# v1.net
KiCad netlist of a schematic drawn in EAGLE
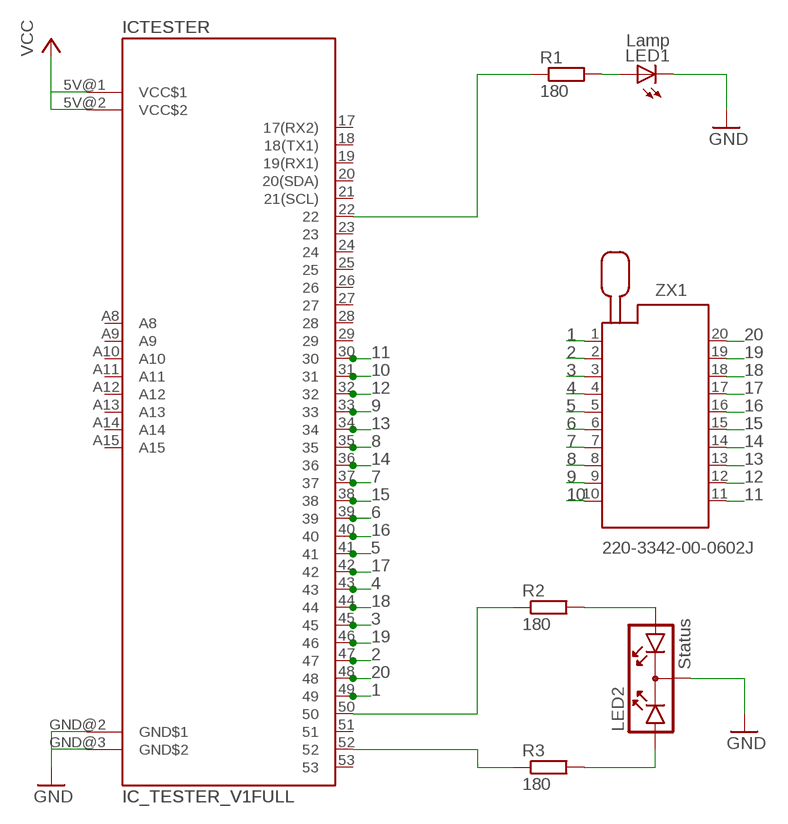
[diagram p0: schematic, sheet 1]

(export (version "E")
  (design (tool "Eeschema 10.0.6"))
  (components
    (comp (ref "ICTESTER")
      (value "IC_TESTER_V1FULL")
      (footprint "eagle-import:SPARKFUN-BOARDS_ARDUINO_MEGA")
      (libsource (lib "eagle-import") (part "IC_TESTER_V1FULL"))
    )
    (comp (ref "LED1")
      (value "Lamp")
      (footprint "eagle-import:LED3MM")
      (libsource (lib "eagle-import") (part "LED3MM"))
    )
    (comp (ref "LED2")
      (value "Status")
      (footprint "eagle-import:DUOLED")
      (libsource (lib "eagle-import") (part "DUOLED"))
    )
    (comp (ref "R1")
      (value "180")
      (footprint "eagle-import:0204V")
      (libsource (lib "eagle-import") (part "R-EU_0204/2V"))
    )
    (comp (ref "R2")
      (value "180")
      (footprint "eagle-import:0204V")
      (libsource (lib "eagle-import") (part "R-EU_0204/2V"))
    )
    (comp (ref "R3")
      (value "180")
      (footprint "eagle-import:0204V")
      (libsource (lib "eagle-import") (part "R-EU_0204/2V"))
    )
    (comp (ref "ZX1")
      (value "220-3342-00-0602J")
      (footprint "eagle-import:220-3342-00-0602J")
      (fields (field (name "MF") "3M"))
      (libsource (lib "eagle-import") (part "220-3342-00-0602J"))
    )
  )
  (nets
    (net (code "1") (name "/1") (class "Default")
      (node (ref "ICTESTER") (pin "49") (pinfunction "49_49") (pintype "bidirectional"))
      (node (ref "ZX1") (pin "1") (pinfunction "1_1") (pintype "passive"))
    )
    (net (code "2") (name "/2") (class "Default")
      (node (ref "ICTESTER") (pin "47") (pinfunction "47_47") (pintype "bidirectional"))
      (node (ref "ZX1") (pin "2") (pinfunction "2_2") (pintype "passive"))
    )
    (net (code "3") (name "/3") (class "Default")
      (node (ref "ICTESTER") (pin "45") (pinfunction "45_45") (pintype "bidirectional"))
      (node (ref "ZX1") (pin "3") (pinfunction "3_3") (pintype "passive"))
    )
    (net (code "4") (name "/4") (class "Default")
      (node (ref "ICTESTER") (pin "43") (pinfunction "43_43") (pintype "bidirectional"))
      (node (ref "ZX1") (pin "4") (pinfunction "4_4") (pintype "passive"))
    )
    (net (code "5") (name "/5") (class "Default")
      (node (ref "ICTESTER") (pin "41") (pinfunction "41_41") (pintype "bidirectional"))
      (node (ref "ZX1") (pin "5") (pinfunction "5_5") (pintype "passive"))
    )
    (net (code "6") (name "/6") (class "Default")
      (node (ref "ICTESTER") (pin "39") (pinfunction "39_39") (pintype "bidirectional"))
      (node (ref "ZX1") (pin "6") (pinfunction "6_6") (pintype "passive"))
    )
    (net (code "7") (name "/7") (class "Default")
      (node (ref "ICTESTER") (pin "37") (pinfunction "37_37") (pintype "bidirectional"))
      (node (ref "ZX1") (pin "7") (pinfunction "7_7") (pintype "passive"))
    )
    (net (code "8") (name "/8") (class "Default")
      (node (ref "ICTESTER") (pin "35") (pinfunction "35_35") (pintype "bidirectional"))
      (node (ref "ZX1") (pin "8") (pinfunction "8_8") (pintype "passive"))
    )
    (net (code "9") (name "/9") (class "Default")
      (node (ref "ICTESTER") (pin "33") (pinfunction "33_33") (pintype "bidirectional"))
      (node (ref "ZX1") (pin "9") (pinfunction "9_9") (pintype "passive"))
    )
    (net (code "10") (name "/10") (class "Default")
      (node (ref "ICTESTER") (pin "31") (pinfunction "31_31") (pintype "bidirectional"))
      (node (ref "ZX1") (pin "10") (pinfunction "10_10") (pintype "passive"))
    )
    (net (code "11") (name "/11") (class "Default")
      (node (ref "ICTESTER") (pin "30") (pinfunction "30_30") (pintype "bidirectional"))
      (node (ref "ZX1") (pin "11") (pinfunction "11_11") (pintype "passive"))
    )
    (net (code "12") (name "/12") (class "Default")
      (node (ref "ICTESTER") (pin "32") (pinfunction "32_32") (pintype "bidirectional"))
      (node (ref "ZX1") (pin "12") (pinfunction "12_12") (pintype "passive"))
    )
    (net (code "13") (name "/13") (class "Default")
      (node (ref "ICTESTER") (pin "34") (pinfunction "34_34") (pintype "bidirectional"))
      (node (ref "ZX1") (pin "13") (pinfunction "13_13") (pintype "passive"))
    )
    (net (code "14") (name "/14") (class "Default")
      (node (ref "ICTESTER") (pin "36") (pinfunction "36_36") (pintype "bidirectional"))
      (node (ref "ZX1") (pin "14") (pinfunction "14_14") (pintype "passive"))
    )
    (net (code "15") (name "/15") (class "Default")
      (node (ref "ICTESTER") (pin "38") (pinfunction "38_38") (pintype "bidirectional"))
      (node (ref "ZX1") (pin "15") (pinfunction "15_15") (pintype "passive"))
    )
    (net (code "16") (name "/16") (class "Default")
      (node (ref "ICTESTER") (pin "40") (pinfunction "40_40") (pintype "bidirectional"))
      (node (ref "ZX1") (pin "16") (pinfunction "16_16") (pintype "passive"))
    )
    (net (code "17") (name "/17") (class "Default")
      (node (ref "ICTESTER") (pin "42") (pinfunction "42_42") (pintype "bidirectional"))
      (node (ref "ZX1") (pin "17") (pinfunction "17_17") (pintype "passive"))
    )
    (net (code "18") (name "/18") (class "Default")
      (node (ref "ICTESTER") (pin "44") (pinfunction "44_44") (pintype "bidirectional"))
      (node (ref "ZX1") (pin "18") (pinfunction "18_18") (pintype "passive"))
    )
    (net (code "19") (name "/19") (class "Default")
      (node (ref "ICTESTER") (pin "46") (pinfunction "46_46") (pintype "bidirectional"))
      (node (ref "ZX1") (pin "19") (pinfunction "19_19") (pintype "passive"))
    )
    (net (code "20") (name "/20") (class "Default")
      (node (ref "ICTESTER") (pin "48") (pinfunction "48_48") (pintype "bidirectional"))
      (node (ref "ZX1") (pin "20") (pinfunction "20_20") (pintype "passive"))
    )
    (net (code "21") (name "GND") (class "Default")
      (node (ref "ICTESTER") (pin "GND@2") (pinfunction "GND$1_GND@2") (pintype "power_in"))
      (node (ref "ICTESTER") (pin "GND@3") (pinfunction "GND$2_GND@3") (pintype "power_in"))
      (node (ref "LED1") (pin "K") (pinfunction "C_K") (pintype "passive"))
      (node (ref "LED2") (pin "K") (pinfunction "K_K") (pintype "passive"))
    )
    (net (code "22") (name "Net-(ICTESTER-Pad22)") (class "Default")
      (node (ref "ICTESTER") (pin "22") (pinfunction "22_22") (pintype "bidirectional"))
      (node (ref "R1") (pin "1") (pinfunction "1_1") (pintype "passive"))
    )
    (net (code "23") (name "Net-(ICTESTER-Pad50)") (class "Default")
      (node (ref "ICTESTER") (pin "50") (pinfunction "50_50") (pintype "bidirectional"))
      (node (ref "R2") (pin "1") (pinfunction "1_1") (pintype "passive"))
    )
    (net (code "24") (name "Net-(ICTESTER-Pad52)") (class "Default")
      (node (ref "ICTESTER") (pin "52") (pinfunction "52_52") (pintype "bidirectional"))
      (node (ref "R3") (pin "1") (pinfunction "1_1") (pintype "passive"))
    )
    (net (code "25") (name "Net-(LED1-PadA)") (class "Default")
      (node (ref "LED1") (pin "A") (pinfunction "A_A") (pintype "passive"))
      (node (ref "R1") (pin "2") (pinfunction "2_2") (pintype "passive"))
    )
    (net (code "26") (name "Net-(LED2-PadA1)") (class "Default")
      (node (ref "LED2") (pin "A1") (pinfunction "A1_A1") (pintype "passive"))
      (node (ref "R3") (pin "2") (pinfunction "2_2") (pintype "passive"))
    )
    (net (code "27") (name "Net-(LED2-PadA2)") (class "Default")
      (node (ref "LED2") (pin "A2") (pinfunction "A2_A2") (pintype "passive"))
      (node (ref "R2") (pin "2") (pinfunction "2_2") (pintype "passive"))
    )
    (net (code "28") (name "VCC") (class "Default")
      (node (ref "ICTESTER") (pin "5V@1") (pinfunction "VCC$1_5V@1") (pintype "power_in"))
      (node (ref "ICTESTER") (pin "5V@2") (pinfunction "VCC$2_5V@2") (pintype "power_in"))
    )
    (net (code "29") (name "unconnected-(ICTESTER-17(RX2)-Pad17)") (class "Default")
      (node (ref "ICTESTER") (pin "17") (pinfunction "17(RX2)_17") (pintype "bidirectional"))
    )
    (net (code "30") (name "unconnected-(ICTESTER-18(TX1)-Pad18)") (class "Default")
      (node (ref "ICTESTER") (pin "18") (pinfunction "18(TX1)_18") (pintype "bidirectional"))
    )
    (net (code "31") (name "unconnected-(ICTESTER-19(RX1)-Pad19)") (class "Default")
      (node (ref "ICTESTER") (pin "19") (pinfunction "19(RX1)_19") (pintype "bidirectional"))
    )
    (net (code "32") (name "unconnected-(ICTESTER-20(SDA)-Pad20)") (class "Default")
      (node (ref "ICTESTER") (pin "20") (pinfunction "20(SDA)_20") (pintype "bidirectional"))
    )
    (net (code "33") (name "unconnected-(ICTESTER-21(SCL)-Pad21)") (class "Default")
      (node (ref "ICTESTER") (pin "21") (pinfunction "21(SCL)_21") (pintype "bidirectional"))
    )
    (net (code "34") (name "unconnected-(ICTESTER-Pad23)") (class "Default")
      (node (ref "ICTESTER") (pin "23") (pinfunction "23_23") (pintype "bidirectional"))
    )
    (net (code "35") (name "unconnected-(ICTESTER-Pad24)") (class "Default")
      (node (ref "ICTESTER") (pin "24") (pinfunction "24_24") (pintype "bidirectional"))
    )
    (net (code "36") (name "unconnected-(ICTESTER-Pad25)") (class "Default")
      (node (ref "ICTESTER") (pin "25") (pinfunction "25_25") (pintype "bidirectional"))
    )
    (net (code "37") (name "unconnected-(ICTESTER-Pad26)") (class "Default")
      (node (ref "ICTESTER") (pin "26") (pinfunction "26_26") (pintype "bidirectional"))
    )
    (net (code "38") (name "unconnected-(ICTESTER-Pad27)") (class "Default")
      (node (ref "ICTESTER") (pin "27") (pinfunction "27_27") (pintype "bidirectional"))
    )
    (net (code "39") (name "unconnected-(ICTESTER-Pad28)") (class "Default")
      (node (ref "ICTESTER") (pin "28") (pinfunction "28_28") (pintype "bidirectional"))
    )
    (net (code "40") (name "unconnected-(ICTESTER-Pad29)") (class "Default")
      (node (ref "ICTESTER") (pin "29") (pinfunction "29_29") (pintype "bidirectional"))
    )
    (net (code "41") (name "unconnected-(ICTESTER-Pad51)") (class "Default")
      (node (ref "ICTESTER") (pin "51") (pinfunction "51_51") (pintype "bidirectional"))
    )
    (net (code "42") (name "unconnected-(ICTESTER-Pad53)") (class "Default")
      (node (ref "ICTESTER") (pin "53") (pinfunction "53_53") (pintype "bidirectional"))
    )
    (net (code "43") (name "unconnected-(ICTESTER-PadA8)") (class "Default")
      (node (ref "ICTESTER") (pin "A8") (pinfunction "A8_A8") (pintype "bidirectional"))
    )
    (net (code "44") (name "unconnected-(ICTESTER-PadA9)") (class "Default")
      (node (ref "ICTESTER") (pin "A9") (pinfunction "A9_A9") (pintype "bidirectional"))
    )
    (net (code "45") (name "unconnected-(ICTESTER-PadA10)") (class "Default")
      (node (ref "ICTESTER") (pin "A10") (pinfunction "A10_A10") (pintype "bidirectional"))
    )
    (net (code "46") (name "unconnected-(ICTESTER-PadA11)") (class "Default")
      (node (ref "ICTESTER") (pin "A11") (pinfunction "A11_A11") (pintype "bidirectional"))
    )
    (net (code "47") (name "unconnected-(ICTESTER-PadA12)") (class "Default")
      (node (ref "ICTESTER") (pin "A12") (pinfunction "A12_A12") (pintype "bidirectional"))
    )
    (net (code "48") (name "unconnected-(ICTESTER-PadA13)") (class "Default")
      (node (ref "ICTESTER") (pin "A13") (pinfunction "A13_A13") (pintype "bidirectional"))
    )
    (net (code "49") (name "unconnected-(ICTESTER-PadA14)") (class "Default")
      (node (ref "ICTESTER") (pin "A14") (pinfunction "A14_A14") (pintype "bidirectional"))
    )
    (net (code "50") (name "unconnected-(ICTESTER-PadA15)") (class "Default")
      (node (ref "ICTESTER") (pin "A15") (pinfunction "A15_A15") (pintype "bidirectional"))
    )
  )
)
